# RobotCtrl_Base_Power.net
KiCad netlist of a schematic drawn in Altium Designer
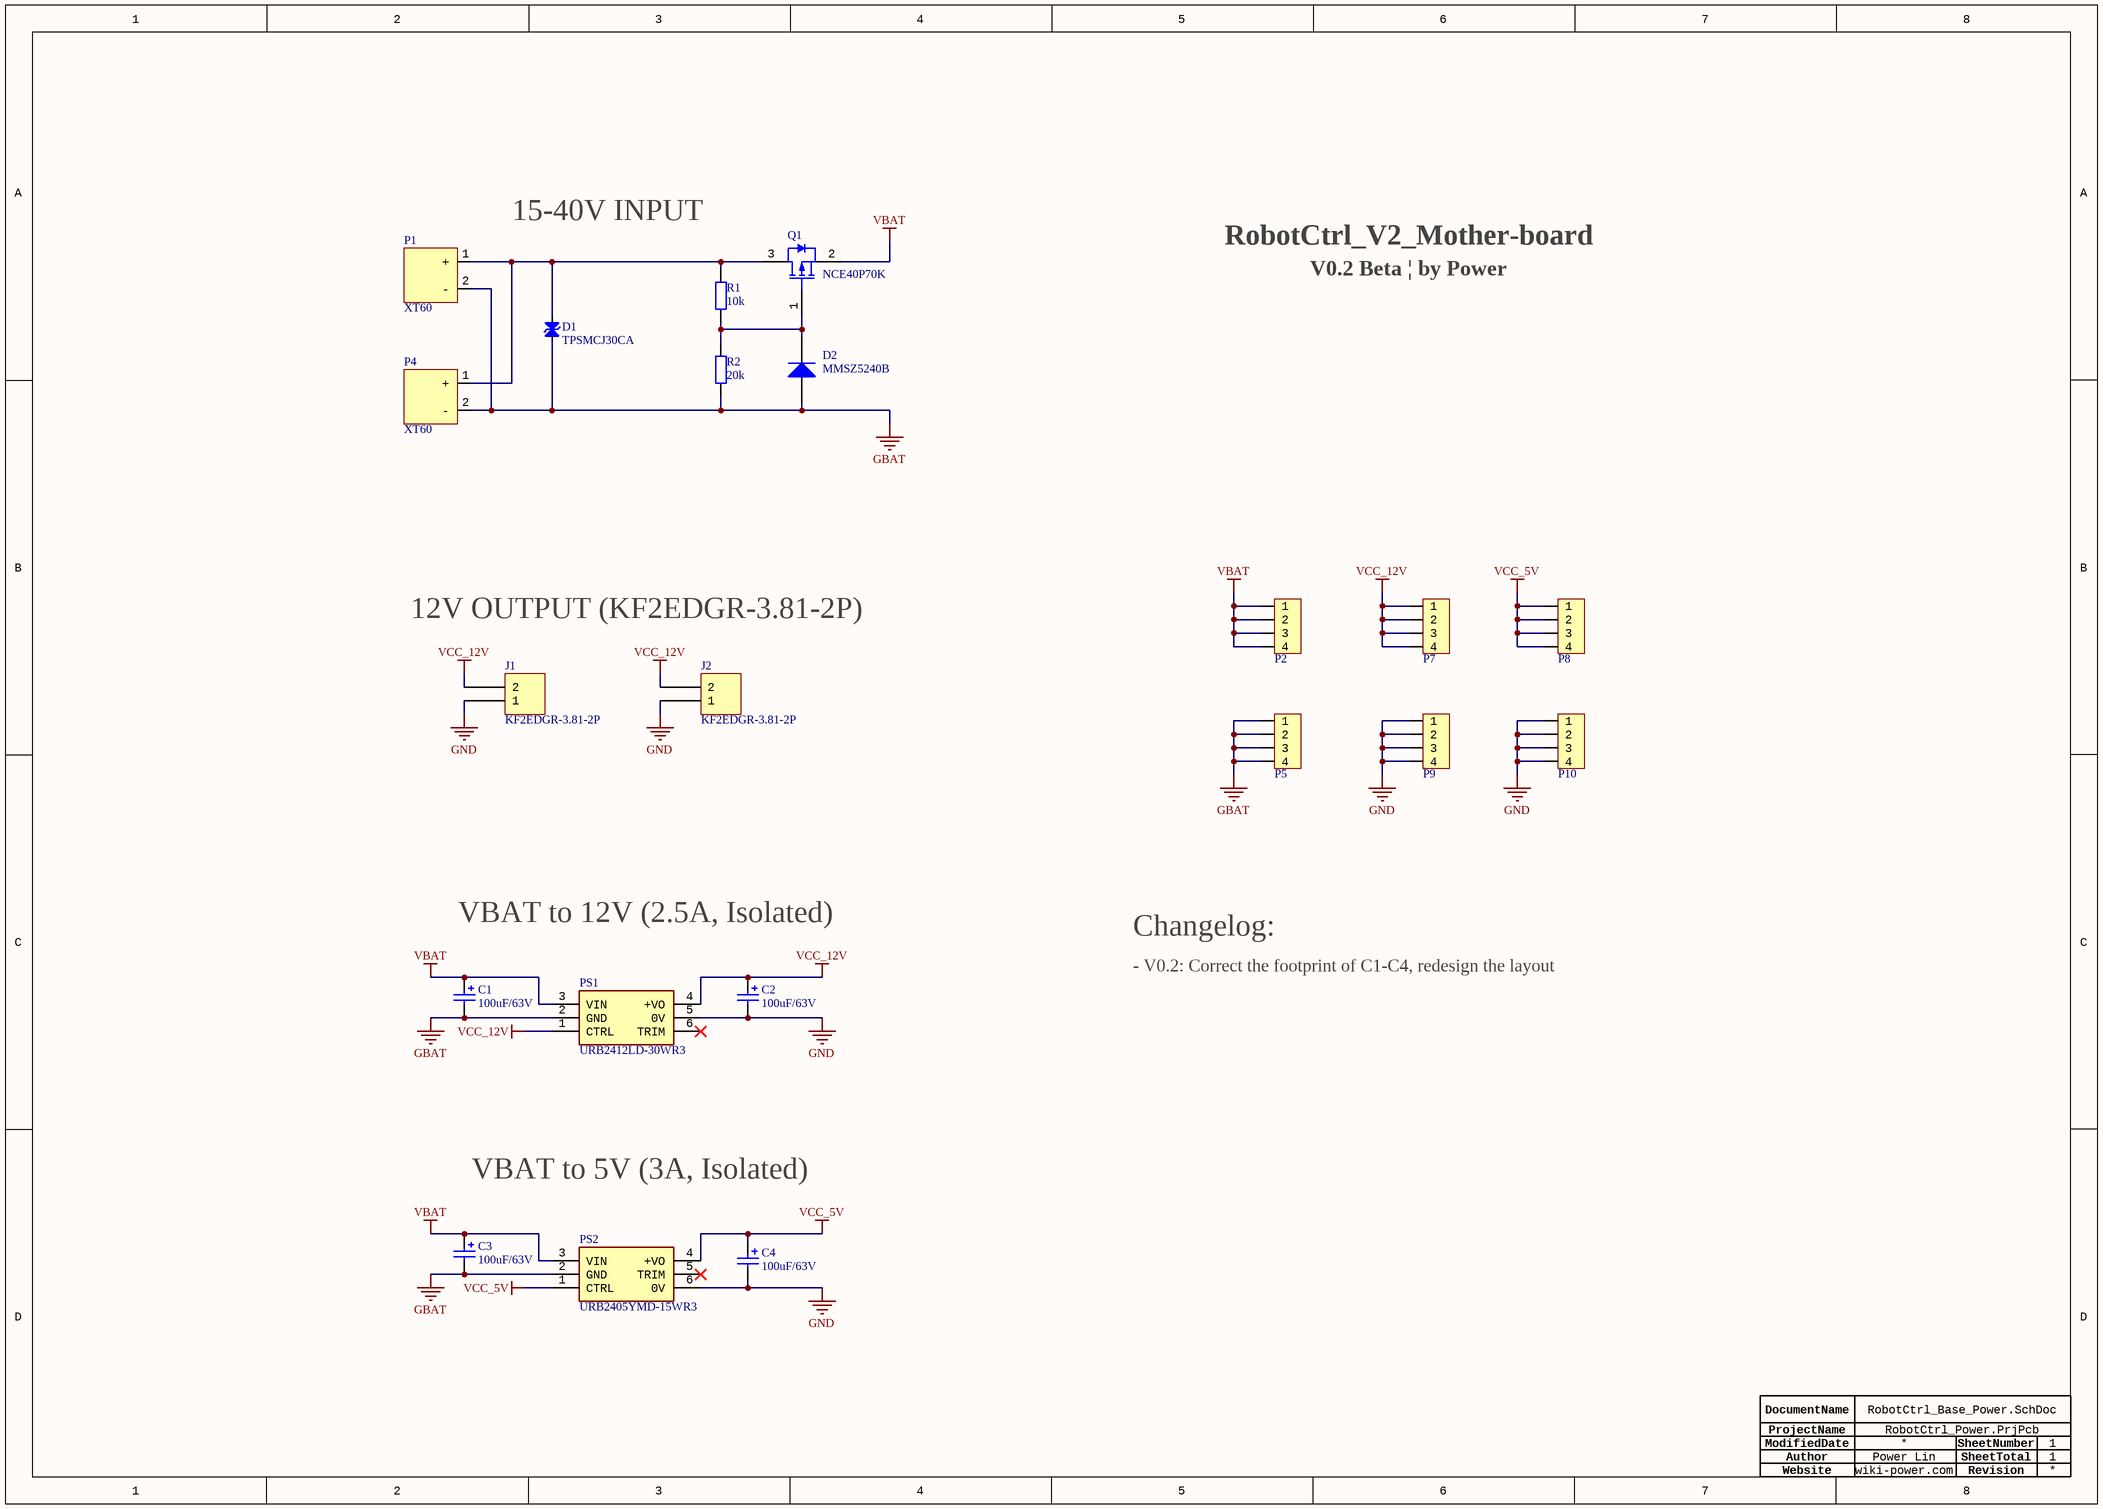
[diagram p0: RobotCtrl_Base_Power.SchDoc]

(export (version "E")
  (design (tool "Eeschema 10.0.6"))
  (components
    (comp (ref "C1")
      (value "100uF/63V")
      (footprint "CAP 3.5*8*11.5")
      (libsource (lib "Power_Lib_Altium") (part "CAP-POL"))
    )
    (comp (ref "C2")
      (value "100uF/63V")
      (footprint "CAP 3.5*8*11.5")
      (libsource (lib "Power_Lib_Altium") (part "CAP-POL"))
    )
    (comp (ref "C3")
      (value "100uF/63V")
      (footprint "CAP 3.5*8*11.5")
      (libsource (lib "Power_Lib_Altium") (part "CAP-POL"))
    )
    (comp (ref "C4")
      (value "100uF/63V")
      (footprint "CAP 3.5*8*11.5")
      (libsource (lib "Power_Lib_Altium") (part "CAP-POL"))
    )
    (comp (ref "D1")
      (value "TPSMCJ30CA")
      (footprint "DO-214AB/SMC")
      (libsource (lib "Power_Lib_Altium") (part "TVS_C"))
    )
    (comp (ref "D2")
      (value "MMSZ5240B")
      (footprint "SOD_123")
      (description "稳压 10V")
      (libsource (lib "Power_Lib_Altium") (part "DIODE"))
    )
    (comp (ref "J1")
      (value "KF2EDGR-3.81-2P")
      (footprint "FCI 06-381-2PIN")
      (description "TERM BLOCK HDR 2POS 90DEG 3.81MM")
      (fields (field (name "PART NUMBER") "OQ0232510000G") (field (name "MANUFACTURER") "Amphenol Anytek"))
      (libsource (lib "Power_Lib_Altium") (part "KF2EDGR-3.81-2P"))
    )
    (comp (ref "J2")
      (value "KF2EDGR-3.81-2P")
      (footprint "FCI 06-381-2PIN")
      (description "TERM BLOCK HDR 2POS 90DEG 3.81MM")
      (fields (field (name "PART NUMBER") "OQ0232510000G") (field (name "MANUFACTURER") "Amphenol Anytek"))
      (libsource (lib "Power_Lib_Altium") (part "KF2EDGR-3.81-2P"))
    )
    (comp (ref "P1")
      (value "XT60")
      (footprint "XT60PW-M")
      (libsource (lib "Power_Lib_Altium") (part "XT30/60"))
    )
    (comp (ref "P2")
      (value "HDR1x4_2.54")
      (footprint "HDR1x4_2.54_180")
      (description "Header")
      (libsource (lib "Power_Lib_Altium") (part "HDR1x4_2.54"))
    )
    (comp (ref "P4")
      (value "XT60")
      (footprint "XT60PW-M")
      (libsource (lib "Power_Lib_Altium") (part "XT30/60"))
    )
    (comp (ref "P5")
      (value "HDR1x4_2.54")
      (footprint "HDR1x4_2.54_180")
      (description "Header")
      (libsource (lib "Power_Lib_Altium") (part "HDR1x4_2.54"))
    )
    (comp (ref "P7")
      (value "HDR1x4_2.54")
      (footprint "HDR1x4_2.54_180")
      (description "Header")
      (libsource (lib "Power_Lib_Altium") (part "HDR1x4_2.54"))
    )
    (comp (ref "P8")
      (value "HDR1x4_2.54")
      (footprint "HDR1x4_2.54_180")
      (description "Header")
      (libsource (lib "Power_Lib_Altium") (part "HDR1x4_2.54"))
    )
    (comp (ref "P9")
      (value "HDR1x4_2.54")
      (footprint "HDR1x4_2.54_180")
      (description "Header")
      (libsource (lib "Power_Lib_Altium") (part "HDR1x4_2.54"))
    )
    (comp (ref "P10")
      (value "HDR1x4_2.54")
      (footprint "HDR1x4_2.54_180")
      (description "Header")
      (libsource (lib "Power_Lib_Altium") (part "HDR1x4_2.54"))
    )
    (comp (ref "PS1")
      (value "URB2412LD-30WR3")
      (footprint "URB2412LD30WR3")
      (description "金升阳隔离电源")
      (fields (field (name "MANUFACTURER_PART_NUMBER") "URB2412LD-30WHR3"))
      (libsource (lib "Power_Lib_Altium") (part "URB2412LD-30WR3"))
    )
    (comp (ref "PS2")
      (value "URB2405YMD-15WR3")
      (footprint "URB2405YMD15WR3")
      (description "金升阳隔离电源")
      (fields (field (name "MANUFACTURER_PART_NUMBER") "URB2405YMD-10WR3"))
      (libsource (lib "Power_Lib_Altium") (part "URB2405YMD-15WR3"))
    )
    (comp (ref "Q1")
      (value "NCE40P70K")
      (footprint "TO-252")
      (fields (field (name "MANUFACTURER") "NCE Power"))
      (libsource (lib "Power_Lib_Altium") (part "P-MOS"))
    )
    (comp (ref "R1")
      (value "10k")
      (footprint "R-0603")
      (description "贴片电阻")
      (libsource (lib "Power_Lib_Altium") (part "RES"))
    )
    (comp (ref "R2")
      (value "20k")
      (footprint "R-0603")
      (description "贴片电阻")
      (libsource (lib "Power_Lib_Altium") (part "RES"))
    )
  )
  (nets
    (net (code "1") (name "GBAT") (class "Default")
      (node (ref "C1") (pin "2") (pinfunction "2_2") (pintype "passive"))
      (node (ref "C3") (pin "2") (pinfunction "2_2") (pintype "passive"))
      (node (ref "D1") (pin "1") (pinfunction "1_1") (pintype "passive"))
      (node (ref "D2") (pin "1") (pinfunction "A_1") (pintype "passive"))
      (node (ref "P1") (pin "2") (pinfunction "-_2") (pintype "passive"))
      (node (ref "P4") (pin "2") (pinfunction "-_2") (pintype "passive"))
      (node (ref "P5") (pin "1") (pinfunction "1_1") (pintype "passive"))
      (node (ref "P5") (pin "2") (pinfunction "2_2") (pintype "passive"))
      (node (ref "P5") (pin "3") (pinfunction "3_3") (pintype "passive"))
      (node (ref "P5") (pin "4") (pinfunction "4_4") (pintype "passive"))
      (node (ref "PS1") (pin "2") (pinfunction "GND_2") (pintype "passive"))
      (node (ref "PS2") (pin "2") (pinfunction "GND_2") (pintype "passive"))
      (node (ref "R2") (pin "2") (pinfunction "2_2") (pintype "passive"))
    )
    (net (code "2") (name "GND") (class "Default")
      (node (ref "C2") (pin "2") (pinfunction "2_2") (pintype "passive"))
      (node (ref "C4") (pin "2") (pinfunction "2_2") (pintype "passive"))
      (node (ref "J1") (pin "1") (pinfunction "1_1") (pintype "passive"))
      (node (ref "J2") (pin "1") (pinfunction "1_1") (pintype "passive"))
      (node (ref "P10") (pin "1") (pinfunction "1_1") (pintype "passive"))
      (node (ref "P10") (pin "2") (pinfunction "2_2") (pintype "passive"))
      (node (ref "P10") (pin "3") (pinfunction "3_3") (pintype "passive"))
      (node (ref "P10") (pin "4") (pinfunction "4_4") (pintype "passive"))
      (node (ref "P9") (pin "1") (pinfunction "1_1") (pintype "passive"))
      (node (ref "P9") (pin "2") (pinfunction "2_2") (pintype "passive"))
      (node (ref "P9") (pin "3") (pinfunction "3_3") (pintype "passive"))
      (node (ref "P9") (pin "4") (pinfunction "4_4") (pintype "passive"))
      (node (ref "PS1") (pin "5") (pinfunction "0V_5") (pintype "passive"))
      (node (ref "PS2") (pin "6") (pinfunction "0V_6") (pintype "passive"))
    )
    (net (code "3") (name "Net-(D2-K)") (class "Default")
      (node (ref "D2") (pin "2") (pinfunction "K_2") (pintype "passive"))
      (node (ref "Q1") (pin "1") (pinfunction "GATE_1") (pintype "passive"))
      (node (ref "R1") (pin "2") (pinfunction "2_2") (pintype "passive"))
      (node (ref "R2") (pin "1") (pinfunction "1_1") (pintype "passive"))
    )
    (net (code "4") (name "Net-(P1-+)") (class "Default")
      (node (ref "D1") (pin "2") (pinfunction "2_2") (pintype "passive"))
      (node (ref "P1") (pin "1") (pinfunction "+_1") (pintype "passive"))
      (node (ref "P4") (pin "1") (pinfunction "+_1") (pintype "passive"))
      (node (ref "Q1") (pin "3") (pinfunction "DRAIN_3") (pintype "passive"))
      (node (ref "R1") (pin "1") (pinfunction "1_1") (pintype "passive"))
    )
    (net (code "5") (name "VBAT") (class "Default")
      (node (ref "C1") (pin "1") (pinfunction "1_1") (pintype "passive"))
      (node (ref "C3") (pin "1") (pinfunction "1_1") (pintype "passive"))
      (node (ref "P2") (pin "1") (pinfunction "1_1") (pintype "passive"))
      (node (ref "P2") (pin "2") (pinfunction "2_2") (pintype "passive"))
      (node (ref "P2") (pin "3") (pinfunction "3_3") (pintype "passive"))
      (node (ref "P2") (pin "4") (pinfunction "4_4") (pintype "passive"))
      (node (ref "PS1") (pin "3") (pinfunction "VIN_3") (pintype "passive"))
      (node (ref "PS2") (pin "3") (pinfunction "VIN_3") (pintype "passive"))
      (node (ref "Q1") (pin "2") (pinfunction "SOURCE_2") (pintype "passive"))
    )
    (net (code "6") (name "VCC_5V") (class "Default")
      (node (ref "C4") (pin "1") (pinfunction "1_1") (pintype "passive"))
      (node (ref "P8") (pin "1") (pinfunction "1_1") (pintype "passive"))
      (node (ref "P8") (pin "2") (pinfunction "2_2") (pintype "passive"))
      (node (ref "P8") (pin "3") (pinfunction "3_3") (pintype "passive"))
      (node (ref "P8") (pin "4") (pinfunction "4_4") (pintype "passive"))
      (node (ref "PS2") (pin "1") (pinfunction "CTRL_1") (pintype "passive"))
      (node (ref "PS2") (pin "4") (pinfunction "+VO_4") (pintype "passive"))
    )
    (net (code "7") (name "VCC_12V") (class "Default")
      (node (ref "C2") (pin "1") (pinfunction "1_1") (pintype "passive"))
      (node (ref "J1") (pin "2") (pinfunction "2_2") (pintype "passive"))
      (node (ref "J2") (pin "2") (pinfunction "2_2") (pintype "passive"))
      (node (ref "P7") (pin "1") (pinfunction "1_1") (pintype "passive"))
      (node (ref "P7") (pin "2") (pinfunction "2_2") (pintype "passive"))
      (node (ref "P7") (pin "3") (pinfunction "3_3") (pintype "passive"))
      (node (ref "P7") (pin "4") (pinfunction "4_4") (pintype "passive"))
      (node (ref "PS1") (pin "1") (pinfunction "CTRL_1") (pintype "passive"))
      (node (ref "PS1") (pin "4") (pinfunction "+VO_4") (pintype "passive"))
    )
    (net (code "8") (name "unconnected-(PS1-TRIM-Pad6)") (class "Default")
      (node (ref "PS1") (pin "6") (pinfunction "TRIM_6") (pintype "passive+no_connect"))
    )
    (net (code "9") (name "unconnected-(PS2-TRIM-Pad5)") (class "Default")
      (node (ref "PS2") (pin "5") (pinfunction "TRIM_5") (pintype "passive+no_connect"))
    )
  )
)
